# PowerSupply.net
KiCad netlist of a schematic drawn in EAGLE
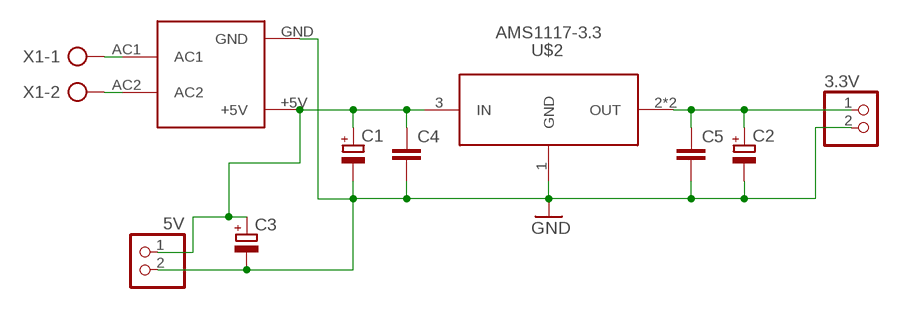
[diagram p0: schematic, sheet 1]

(export (version "E")
  (design (tool "Eeschema 10.0.6"))
  (components
    (comp (ref "3.3V")
      (value "PINHD-1X2")
      (footprint "eagle-import:1X02")
      (libsource (lib "eagle-import") (part "PINHD-1X2"))
    )
    (comp (ref "5V")
      (value "PINHD-1X2")
      (footprint "eagle-import:1X02")
      (libsource (lib "eagle-import") (part "PINHD-1X2"))
    )
    (comp (ref "C1")
      (value "CPOL-EUB/3528-21R")
      (footprint "eagle-import:B_3528-21R")
      (libsource (lib "eagle-import") (part "CPOL-EUB/3528-21R"))
    )
    (comp (ref "C2")
      (value "CPOL-EUB/3528-21R")
      (footprint "eagle-import:B_3528-21R")
      (libsource (lib "eagle-import") (part "CPOL-EUB/3528-21R"))
    )
    (comp (ref "C3")
      (value "CPOL-EUE2-5")
      (footprint "eagle-import:E2-5")
      (libsource (lib "eagle-import") (part "CPOL-EUE2-5"))
    )
    (comp (ref "C4")
      (value "C-EUC0805K")
      (footprint "eagle-import:C0805K")
      (libsource (lib "eagle-import") (part "C-EUC0805K"))
    )
    (comp (ref "C5")
      (value "C-EUC0805K")
      (footprint "eagle-import:C0805K")
      (libsource (lib "eagle-import") (part "C-EUC0805K"))
    )
    (comp (ref "U$1")
      (value "HLK-PM01")
      (footprint "eagle-import:HLK-PM01")
      (libsource (lib "eagle-import") (part "HLK-PM01"))
    )
    (comp (ref "U$2")
      (value "AMS1117-3.3")
      (footprint "eagle-import:SOT-223")
      (libsource (lib "eagle-import") (part "AMS1117-3.3"))
    )
    (comp (ref "X1")
      (value "AK300/2")
      (footprint "eagle-import:AK300_2")
      (libsource (lib "eagle-import") (part "AK300/2"))
    )
  )
  (nets
    (net (code "1") (name "GND") (class "Default")
      (node (ref "3.3V") (pin "2") (pinfunction "2_2") (pintype "passive"))
      (node (ref "5V") (pin "2") (pinfunction "2_2") (pintype "passive"))
      (node (ref "C1") (pin "-") (pinfunction "-_-") (pintype "passive"))
      (node (ref "C2") (pin "-") (pinfunction "-_-") (pintype "passive"))
      (node (ref "C3") (pin "-") (pinfunction "-_-") (pintype "passive"))
      (node (ref "C4") (pin "2") (pinfunction "2_2") (pintype "passive"))
      (node (ref "C5") (pin "2") (pinfunction "2_2") (pintype "passive"))
      (node (ref "U$1") (pin "GND") (pinfunction "GND_GND") (pintype "bidirectional"))
      (node (ref "U$2") (pin "1") (pinfunction "GND_1") (pintype "passive"))
    )
    (net (code "2") (name "Net-(3.3V-Pad1)") (class "Default")
      (node (ref "3.3V") (pin "1") (pinfunction "1_1") (pintype "passive"))
      (node (ref "C2") (pin "+") (pinfunction "+_+") (pintype "passive"))
      (node (ref "C5") (pin "1") (pinfunction "1_1") (pintype "passive"))
      (node (ref "U$2") (pin "2") (pinfunction "OUT_2") (pintype "output"))
      (node (ref "U$2") (pin "4") (pinfunction "OUT_4") (pintype "output"))
    )
    (net (code "3") (name "Net-(U$2-IN)") (class "Default")
      (node (ref "5V") (pin "1") (pinfunction "1_1") (pintype "passive"))
      (node (ref "C1") (pin "+") (pinfunction "+_+") (pintype "passive"))
      (node (ref "C3") (pin "+") (pinfunction "+_+") (pintype "passive"))
      (node (ref "C4") (pin "1") (pinfunction "1_1") (pintype "passive"))
      (node (ref "U$1") (pin "+5V") (pinfunction "+5V_+5V") (pintype "bidirectional"))
      (node (ref "U$2") (pin "3") (pinfunction "IN_3") (pintype "input"))
    )
    (net (code "4") (name "Net-(X1A-KL)") (class "Default")
      (node (ref "U$1") (pin "AC1") (pinfunction "AC1_AC1") (pintype "bidirectional"))
      (node (ref "X1") (pin "1") (pinfunction "KL_1") (pintype "passive"))
    )
    (net (code "5") (name "Net-(X1B-KL)") (class "Default")
      (node (ref "U$1") (pin "AC2") (pinfunction "AC2_AC2") (pintype "bidirectional"))
      (node (ref "X1") (pin "2") (pinfunction "KL_2") (pintype "passive"))
    )
  )
)
